# HIRIMINI-BANTAM.net
KiCad netlist of a schematic drawn in EAGLE
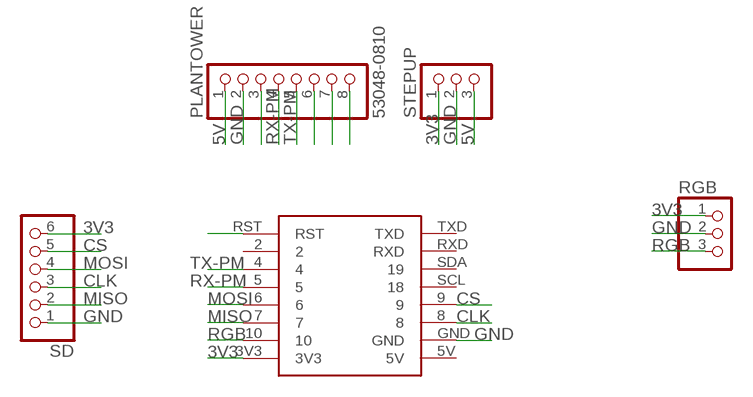
[diagram p0: schematic, sheet 1]

(export (version "E")
  (design (tool "Eeschema 10.0.6"))
  (components
    (comp (ref "PLANTOWER")
      (value "53048-0810")
      (footprint "eagle-import:MOLEX_53048-0810")
      (fields (field (name "MF") "Molex"))
      (libsource (lib "eagle-import") (part "53048-0810"))
    )
    (comp (ref "RGB")
      (value "PINHD-1X3")
      (footprint "eagle-import:1X03")
      (libsource (lib "eagle-import") (part "PINHD-1X3"))
    )
    (comp (ref "SD")
      (value "PINHD-1X6")
      (footprint "eagle-import:1X06")
      (libsource (lib "eagle-import") (part "PINHD-1X6"))
    )
    (comp (ref "STEPUP")
      (value "PINHD-1X3")
      (footprint "eagle-import:1X03")
      (libsource (lib "eagle-import") (part "PINHD-1X3"))
    )
    (comp (ref "U$2")
      (value "LILYGOPLUSMINI")
      (footprint "eagle-import:LILYGO-PADS")
      (libsource (lib "eagle-import") (part "LILYGOPLUSMINI"))
    )
  )
  (nets
    (net (code "1") (name "/3V3") (class "Default")
      (node (ref "RGB") (pin "1") (pinfunction "1_1") (pintype "passive"))
      (node (ref "SD") (pin "6") (pinfunction "6_6") (pintype "passive"))
      (node (ref "STEPUP") (pin "1") (pinfunction "1_1") (pintype "passive"))
      (node (ref "U$2") (pin "3V3") (pinfunction "3V3_3V3") (pintype "bidirectional"))
    )
    (net (code "2") (name "/5V") (class "Default")
      (node (ref "PLANTOWER") (pin "1") (pinfunction "1_1") (pintype "passive"))
      (node (ref "STEPUP") (pin "3") (pinfunction "3_3") (pintype "passive"))
    )
    (net (code "3") (name "/CLK") (class "Default")
      (node (ref "SD") (pin "3") (pinfunction "3_3") (pintype "passive"))
      (node (ref "U$2") (pin "8") (pinfunction "8_8") (pintype "bidirectional"))
    )
    (net (code "4") (name "/CS") (class "Default")
      (node (ref "SD") (pin "5") (pinfunction "5_5") (pintype "passive"))
      (node (ref "U$2") (pin "9") (pinfunction "9_9") (pintype "bidirectional"))
    )
    (net (code "5") (name "/GND") (class "Default")
      (node (ref "PLANTOWER") (pin "2") (pinfunction "2_2") (pintype "passive"))
      (node (ref "RGB") (pin "2") (pinfunction "2_2") (pintype "passive"))
      (node (ref "SD") (pin "1") (pinfunction "1_1") (pintype "passive"))
      (node (ref "STEPUP") (pin "2") (pinfunction "2_2") (pintype "passive"))
      (node (ref "U$2") (pin "GND") (pinfunction "GND_GND") (pintype "bidirectional"))
    )
    (net (code "6") (name "/MISO") (class "Default")
      (node (ref "SD") (pin "2") (pinfunction "2_2") (pintype "passive"))
      (node (ref "U$2") (pin "7") (pinfunction "7_7") (pintype "bidirectional"))
    )
    (net (code "7") (name "/MOSI") (class "Default")
      (node (ref "SD") (pin "4") (pinfunction "4_4") (pintype "passive"))
      (node (ref "U$2") (pin "6") (pinfunction "6_6") (pintype "bidirectional"))
    )
    (net (code "8") (name "/RGB") (class "Default")
      (node (ref "RGB") (pin "3") (pinfunction "3_3") (pintype "passive"))
      (node (ref "U$2") (pin "10") (pinfunction "10_10") (pintype "bidirectional"))
    )
    (net (code "9") (name "/RX-PM") (class "Default")
      (node (ref "PLANTOWER") (pin "4") (pinfunction "4_4") (pintype "passive"))
      (node (ref "U$2") (pin "5") (pinfunction "5_5") (pintype "bidirectional"))
    )
    (net (code "10") (name "/TX-PM") (class "Default")
      (node (ref "PLANTOWER") (pin "5") (pinfunction "5_5") (pintype "passive"))
      (node (ref "U$2") (pin "4") (pinfunction "4_4") (pintype "bidirectional"))
    )
    (net (code "11") (name "unconnected-(PLANTOWER-Pad3)") (class "Default")
      (node (ref "PLANTOWER") (pin "3") (pinfunction "3_3") (pintype "passive"))
    )
    (net (code "12") (name "unconnected-(PLANTOWER-Pad6)") (class "Default")
      (node (ref "PLANTOWER") (pin "6") (pinfunction "6_6") (pintype "passive"))
    )
    (net (code "13") (name "unconnected-(PLANTOWER-Pad7)") (class "Default")
      (node (ref "PLANTOWER") (pin "7") (pinfunction "7_7") (pintype "passive"))
    )
    (net (code "14") (name "unconnected-(PLANTOWER-Pad8)") (class "Default")
      (node (ref "PLANTOWER") (pin "8") (pinfunction "8_8") (pintype "passive"))
    )
    (net (code "15") (name "unconnected-(U$2-18-PadSCL)") (class "Default")
      (node (ref "U$2") (pin "SCL") (pinfunction "18_SCL") (pintype "bidirectional"))
    )
    (net (code "16") (name "unconnected-(U$2-19-PadSDA)") (class "Default")
      (node (ref "U$2") (pin "SDA") (pinfunction "19_SDA") (pintype "bidirectional"))
    )
    (net (code "17") (name "unconnected-(U$2-Pad2)") (class "Default")
      (node (ref "U$2") (pin "2") (pinfunction "2_2") (pintype "bidirectional"))
    )
    (net (code "18") (name "unconnected-(U$2-Pad5V)") (class "Default")
      (node (ref "U$2") (pin "5V") (pinfunction "5V_5V") (pintype "bidirectional"))
    )
    (net (code "19") (name "unconnected-(U$2-PadRST)") (class "Default")
      (node (ref "U$2") (pin "RST") (pinfunction "RST_RST") (pintype "bidirectional"))
    )
    (net (code "20") (name "unconnected-(U$2-PadRXD)") (class "Default")
      (node (ref "U$2") (pin "RXD") (pinfunction "RXD_RXD") (pintype "bidirectional"))
    )
    (net (code "21") (name "unconnected-(U$2-PadTXD)") (class "Default")
      (node (ref "U$2") (pin "TXD") (pinfunction "TXD_TXD") (pintype "bidirectional"))
    )
  )
)
